# sch.net
KiCad netlist of a schematic drawn in Altium Designer
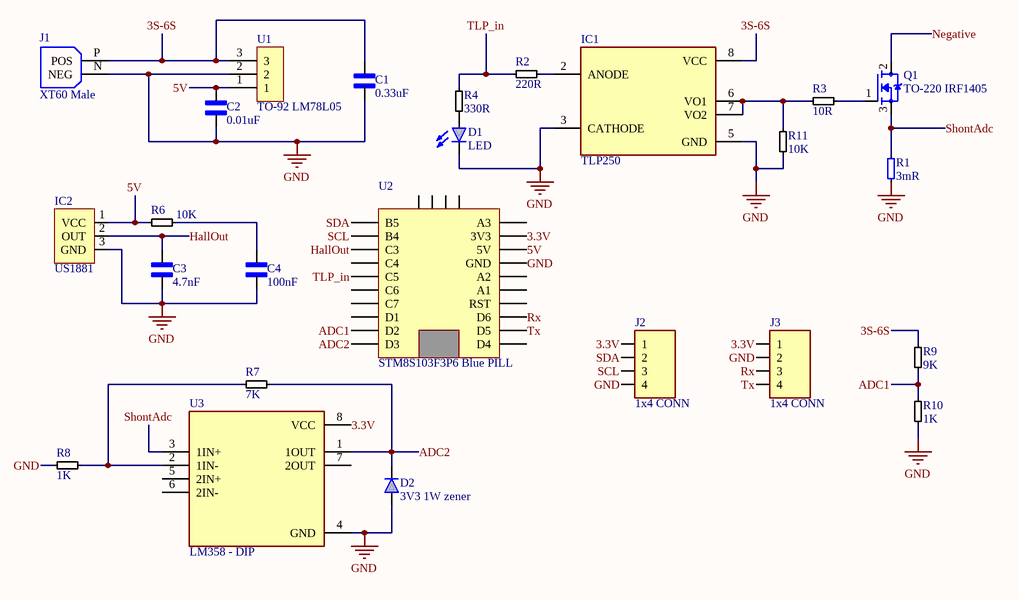
[diagram p0: sch.SchDoc]

(export (version "E")
  (design (tool "Eeschema 10.0.6"))
  (components
    (comp (ref "C1")
      (value "0.33uF")
      (footprint "CER-DIP-CAP")
      (libsource (lib "MYS-Library") (part "CAP DIP"))
    )
    (comp (ref "C2")
      (value "0.01uF")
      (footprint "CER-DIP-CAP")
      (libsource (lib "MYS-Library") (part "CAP DIP"))
    )
    (comp (ref "C3")
      (value "4.7nF")
      (footprint "CER-DIP-CAP")
      (libsource (lib "MYS-Library") (part "CAP DIP"))
    )
    (comp (ref "C4")
      (value "100nF")
      (footprint "CER-DIP-CAP")
      (libsource (lib "MYS-Library") (part "CAP DIP"))
    )
    (comp (ref "D1") (value "LED") (footprint "LED DIP") (libsource (lib "MYS-Library") (part "LED DIP")))
    (comp (ref "D2")
      (value "3V3 1W zener")
      (footprint "1N4001")
      (description "Diode")
      (libsource (lib "MYS-Library") (part "1N4001"))
    )
    (comp (ref "IC1")
      (value "TLP250")
      (footprint "DIP-8")
      (libsource (lib "MYS-Library") (part "TLP250-DIP"))
    )
    (comp (ref "IC2") (value "US1881") (footprint "UA") (libsource (lib "MYS-Library") (part "US1881")))
    (comp (ref "J1")
      (value "XT60 Male")
      (footprint "XT60 Male Pin")
      (libsource (lib "MYS-Library") (part "XT60 Male Pin"))
    )
    (comp (ref "J2")
      (value "1x4 CONN")
      (footprint "CON1x4_2.54MM")
      (libsource (lib "MYS-Library") (part "CON1x4_2.54mm"))
    )
    (comp (ref "J3")
      (value "1x4 CONN")
      (footprint "CON1x4_2.54MM")
      (libsource (lib "MYS-Library") (part "CON1x4_2.54mm"))
    )
    (comp (ref "Q1")
      (value "TO-220 IRF1405")
      (footprint "TO-220")
      (libsource (lib "MYS-Library") (part "TO-220 MOSFET"))
    )
    (comp (ref "R1")
      (value "3mR")
      (footprint "RES 2512 SMD")
      (libsource (lib "MYS-Library") (part "RES SMD 2512 SHUNT"))
    )
    (comp (ref "R2") (value "220R") (footprint "RES DIP") (libsource (lib "MYS-Library") (part "RES DIP")))
    (comp (ref "R3") (value "10R") (footprint "RES DIP") (libsource (lib "MYS-Library") (part "RES DIP")))
    (comp (ref "R4") (value "330R") (footprint "RES DIP") (libsource (lib "MYS-Library") (part "RES DIP")))
    (comp (ref "R6") (value "10K") (footprint "RES DIP") (libsource (lib "MYS-Library") (part "RES DIP")))
    (comp (ref "R7") (value "7K") (footprint "RES DIP") (libsource (lib "MYS-Library") (part "RES DIP")))
    (comp (ref "R8") (value "1K") (footprint "RES DIP") (libsource (lib "MYS-Library") (part "RES DIP")))
    (comp (ref "R9") (value "9K") (footprint "RES DIP") (libsource (lib "MYS-Library") (part "RES DIP")))
    (comp (ref "R10") (value "1K") (footprint "RES DIP") (libsource (lib "MYS-Library") (part "RES DIP")))
    (comp (ref "R11") (value "10K") (footprint "RES DIP") (libsource (lib "MYS-Library") (part "RES DIP")))
    (comp (ref "U1")
      (value "TO-92 LM78L05")
      (footprint "TO-226 TO-92")
      (libsource (lib "MYS-Library") (part "TO-92"))
    )
    (comp (ref "U2")
      (value "STM8S103F3P6 Blue PILL")
      (footprint "STM8S103F3P6 BLUE PILL")
      (libsource (lib "MYS-Library") (part "STM8S103F3P6 BLUE PILL"))
    )
    (comp (ref "U3")
      (value "LM358 - DIP")
      (footprint "PDIP-8")
      (libsource (lib "MYS-Library") (part "LM358 - DIP"))
    )
  )
  (nets
    (net (code "1") (name "/3.3V") (class "Default")
      (node (ref "J2") (pin "1") (pinfunction "1_1") (pintype "passive"))
      (node (ref "J3") (pin "1") (pinfunction "1_1") (pintype "passive"))
      (node (ref "U2") (pin "12") (pinfunction "3V3_12") (pintype "passive"))
      (node (ref "U3") (pin "8") (pinfunction "VCC_8") (pintype "passive"))
    )
    (net (code "2") (name "/3S-6S") (class "Default")
      (node (ref "C1") (pin "2") (pinfunction "2_2") (pintype "passive"))
      (node (ref "IC1") (pin "8") (pinfunction "VCC_8") (pintype "power_in"))
      (node (ref "J1") (pin "P") (pinfunction "POS_P") (pintype "passive"))
      (node (ref "R9") (pin "2") (pinfunction "2_2") (pintype "passive"))
      (node (ref "U1") (pin "3") (pinfunction "3_3") (pintype "passive"))
    )
    (net (code "3") (name "/5V") (class "Default")
      (node (ref "C2") (pin "2") (pinfunction "2_2") (pintype "passive"))
      (node (ref "IC2") (pin "1") (pinfunction "VCC_1") (pintype "passive"))
      (node (ref "R6") (pin "1") (pinfunction "1_1") (pintype "passive"))
      (node (ref "U1") (pin "1") (pinfunction "1_1") (pintype "passive"))
      (node (ref "U2") (pin "13") (pinfunction "5V_13") (pintype "passive"))
    )
    (net (code "4") (name "/ADC1") (class "Default")
      (node (ref "R10") (pin "2") (pinfunction "2_2") (pintype "passive"))
      (node (ref "R9") (pin "1") (pinfunction "1_1") (pintype "passive"))
      (node (ref "U2") (pin "9") (pinfunction "D2_9") (pintype "passive"))
    )
    (net (code "5") (name "/ADC2") (class "Default")
      (node (ref "D2") (pin "C") (pinfunction "CATHODE_C") (pintype "passive"))
      (node (ref "R7") (pin "1") (pinfunction "1_1") (pintype "passive"))
      (node (ref "U2") (pin "10") (pinfunction "D3_10") (pintype "passive"))
      (node (ref "U3") (pin "1") (pinfunction "1OUT_1") (pintype "passive"))
    )
    (net (code "6") (name "/HallOut") (class "Default")
      (node (ref "C3") (pin "2") (pinfunction "2_2") (pintype "passive"))
      (node (ref "IC2") (pin "2") (pinfunction "OUT_2") (pintype "passive"))
      (node (ref "U2") (pin "3") (pinfunction "C3_3") (pintype "passive"))
    )
    (net (code "7") (name "/Negative") (class "Default")
      (node (ref "Q1") (pin "2") (pinfunction "D_2") (pintype "passive"))
    )
    (net (code "8") (name "/Rx") (class "Default")
      (node (ref "J3") (pin "3") (pinfunction "3_3") (pintype "passive"))
      (node (ref "U2") (pin "18") (pinfunction "D6_18") (pintype "passive"))
    )
    (net (code "9") (name "/SCL") (class "Default")
      (node (ref "J2") (pin "3") (pinfunction "3_3") (pintype "passive"))
      (node (ref "U2") (pin "2") (pinfunction "B4_2") (pintype "passive"))
    )
    (net (code "10") (name "/SDA") (class "Default")
      (node (ref "J2") (pin "2") (pinfunction "2_2") (pintype "passive"))
      (node (ref "U2") (pin "1") (pinfunction "B5_1") (pintype "passive"))
    )
    (net (code "11") (name "/ShontAdc") (class "Default")
      (node (ref "Q1") (pin "3") (pinfunction "S_3") (pintype "passive"))
      (node (ref "R1") (pin "2") (pinfunction "2_2") (pintype "passive"))
      (node (ref "U3") (pin "3") (pinfunction "1IN+_3") (pintype "passive"))
    )
    (net (code "12") (name "/TLP_in") (class "Default")
      (node (ref "R2") (pin "1") (pinfunction "1_1") (pintype "passive"))
      (node (ref "R4") (pin "1") (pinfunction "1_1") (pintype "passive"))
      (node (ref "U2") (pin "5") (pinfunction "C5_5") (pintype "passive"))
    )
    (net (code "13") (name "/Tx") (class "Default")
      (node (ref "J3") (pin "4") (pinfunction "4_4") (pintype "passive"))
      (node (ref "U2") (pin "19") (pinfunction "D5_19") (pintype "passive"))
    )
    (net (code "14") (name "GND") (class "Default")
      (node (ref "C1") (pin "1") (pinfunction "1_1") (pintype "passive"))
      (node (ref "C2") (pin "1") (pinfunction "1_1") (pintype "passive"))
      (node (ref "C3") (pin "1") (pinfunction "1_1") (pintype "passive"))
      (node (ref "C4") (pin "1") (pinfunction "1_1") (pintype "passive"))
      (node (ref "D1") (pin "C") (pinfunction "C_C") (pintype "passive"))
      (node (ref "D2") (pin "A") (pinfunction "ANODE_A") (pintype "passive"))
      (node (ref "IC1") (pin "3") (pinfunction "CATHODE_3") (pintype "passive"))
      (node (ref "IC1") (pin "5") (pinfunction "GND_5") (pintype "power_in"))
      (node (ref "IC2") (pin "3") (pinfunction "GND_3") (pintype "passive"))
      (node (ref "J1") (pin "N") (pinfunction "NEG_N") (pintype "passive"))
      (node (ref "J2") (pin "4") (pinfunction "4_4") (pintype "passive"))
      (node (ref "J3") (pin "2") (pinfunction "2_2") (pintype "passive"))
      (node (ref "R1") (pin "1") (pinfunction "1_1") (pintype "passive"))
      (node (ref "R10") (pin "1") (pinfunction "1_1") (pintype "passive"))
      (node (ref "R11") (pin "2") (pinfunction "2_2") (pintype "passive"))
      (node (ref "R8") (pin "2") (pinfunction "2_2") (pintype "passive"))
      (node (ref "U1") (pin "2") (pinfunction "2_2") (pintype "passive"))
      (node (ref "U2") (pin "14") (pinfunction "GND_14") (pintype "passive"))
      (node (ref "U3") (pin "4") (pinfunction "GND_4") (pintype "passive"))
    )
    (net (code "15") (name "Net-(C4-Pad2)") (class "Default")
      (node (ref "C4") (pin "2") (pinfunction "2_2") (pintype "passive"))
      (node (ref "R6") (pin "2") (pinfunction "2_2") (pintype "passive"))
    )
    (net (code "16") (name "Net-(D1-PadA)") (class "Default")
      (node (ref "D1") (pin "A") (pinfunction "A_A") (pintype "passive"))
      (node (ref "R4") (pin "2") (pinfunction "2_2") (pintype "passive"))
    )
    (net (code "17") (name "Net-(IC1-ANODE)") (class "Default")
      (node (ref "IC1") (pin "2") (pinfunction "ANODE_2") (pintype "passive"))
      (node (ref "R2") (pin "2") (pinfunction "2_2") (pintype "passive"))
    )
    (net (code "18") (name "Net-(IC1-VO1)") (class "Default")
      (node (ref "IC1") (pin "6") (pinfunction "VO1_6") (pintype "passive"))
      (node (ref "IC1") (pin "7") (pinfunction "VO2_7") (pintype "passive"))
      (node (ref "R11") (pin "1") (pinfunction "1_1") (pintype "passive"))
      (node (ref "R3") (pin "1") (pinfunction "1_1") (pintype "passive"))
    )
    (net (code "19") (name "Net-(Q1-G)") (class "Default")
      (node (ref "Q1") (pin "1") (pinfunction "G_1") (pintype "passive"))
      (node (ref "R3") (pin "2") (pinfunction "2_2") (pintype "passive"))
    )
    (net (code "20") (name "Net-(U3-1IN-)") (class "Default")
      (node (ref "R7") (pin "2") (pinfunction "2_2") (pintype "passive"))
      (node (ref "R8") (pin "1") (pinfunction "1_1") (pintype "passive"))
      (node (ref "U3") (pin "2") (pinfunction "1IN-_2") (pintype "passive"))
    )
    (net (code "21") (name "unconnected-(U2-A1-Pad16)") (class "Default")
      (node (ref "U2") (pin "16") (pinfunction "A1_16") (pintype "passive"))
    )
    (net (code "22") (name "unconnected-(U2-A2-Pad15)") (class "Default")
      (node (ref "U2") (pin "15") (pinfunction "A2_15") (pintype "passive"))
    )
    (net (code "23") (name "unconnected-(U2-A3-Pad11)") (class "Default")
      (node (ref "U2") (pin "11") (pinfunction "A3_11") (pintype "passive"))
    )
    (net (code "24") (name "unconnected-(U2-C4-Pad4)") (class "Default")
      (node (ref "U2") (pin "4") (pinfunction "C4_4") (pintype "passive"))
    )
    (net (code "25") (name "unconnected-(U2-C6-Pad6)") (class "Default")
      (node (ref "U2") (pin "6") (pinfunction "C6_6") (pintype "passive"))
    )
    (net (code "26") (name "unconnected-(U2-C7-Pad7)") (class "Default")
      (node (ref "U2") (pin "7") (pinfunction "C7_7") (pintype "passive"))
    )
    (net (code "27") (name "unconnected-(U2-D1-Pad8)") (class "Default")
      (node (ref "U2") (pin "8") (pinfunction "D1_8") (pintype "passive"))
    )
    (net (code "28") (name "unconnected-(U2-D4-Pad20)") (class "Default")
      (node (ref "U2") (pin "20") (pinfunction "D4_20") (pintype "passive"))
    )
    (net (code "29") (name "unconnected-(U2-RST-Pad17)") (class "Default")
      (node (ref "U2") (pin "17") (pinfunction "RST_17") (pintype "passive"))
    )
    (net (code "30") (name "unconnected-(U3-2IN+-Pad5)") (class "Default")
      (node (ref "U3") (pin "5") (pinfunction "2IN+_5") (pintype "passive"))
    )
    (net (code "31") (name "unconnected-(U3-2IN--Pad6)") (class "Default")
      (node (ref "U3") (pin "6") (pinfunction "2IN-_6") (pintype "passive"))
    )
    (net (code "32") (name "unconnected-(U3-2OUT-Pad7)") (class "Default")
      (node (ref "U3") (pin "7") (pinfunction "2OUT_7") (pintype "passive"))
    )
  )
)
